# Controller.net
KiCad netlist of a schematic drawn in EAGLE
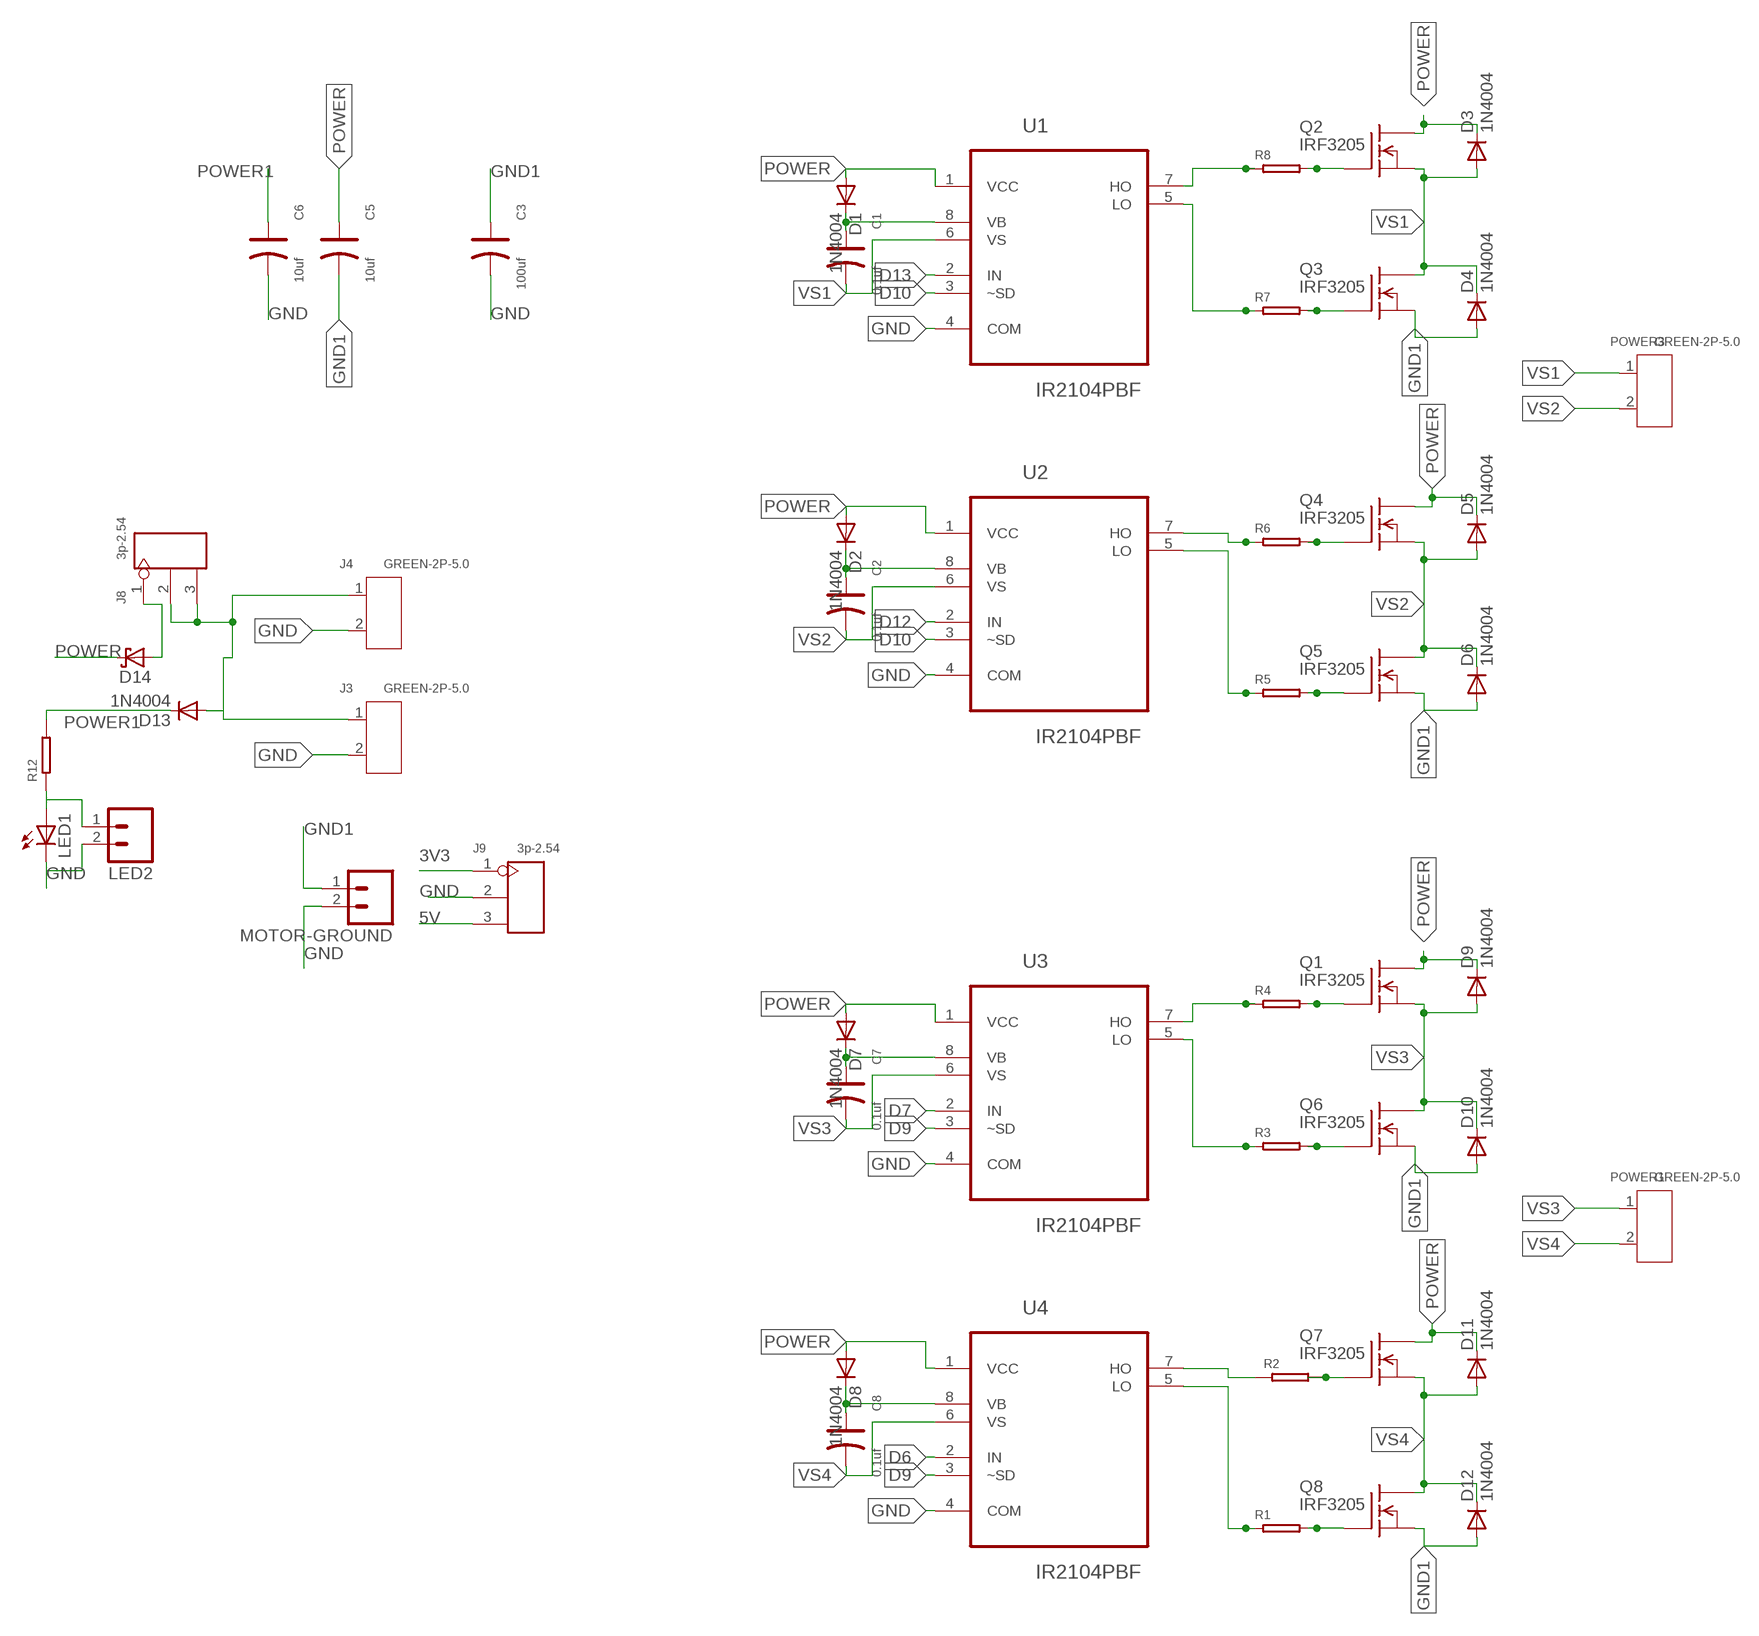
[diagram p0: schematic, sheet 1, part 1 of 2]
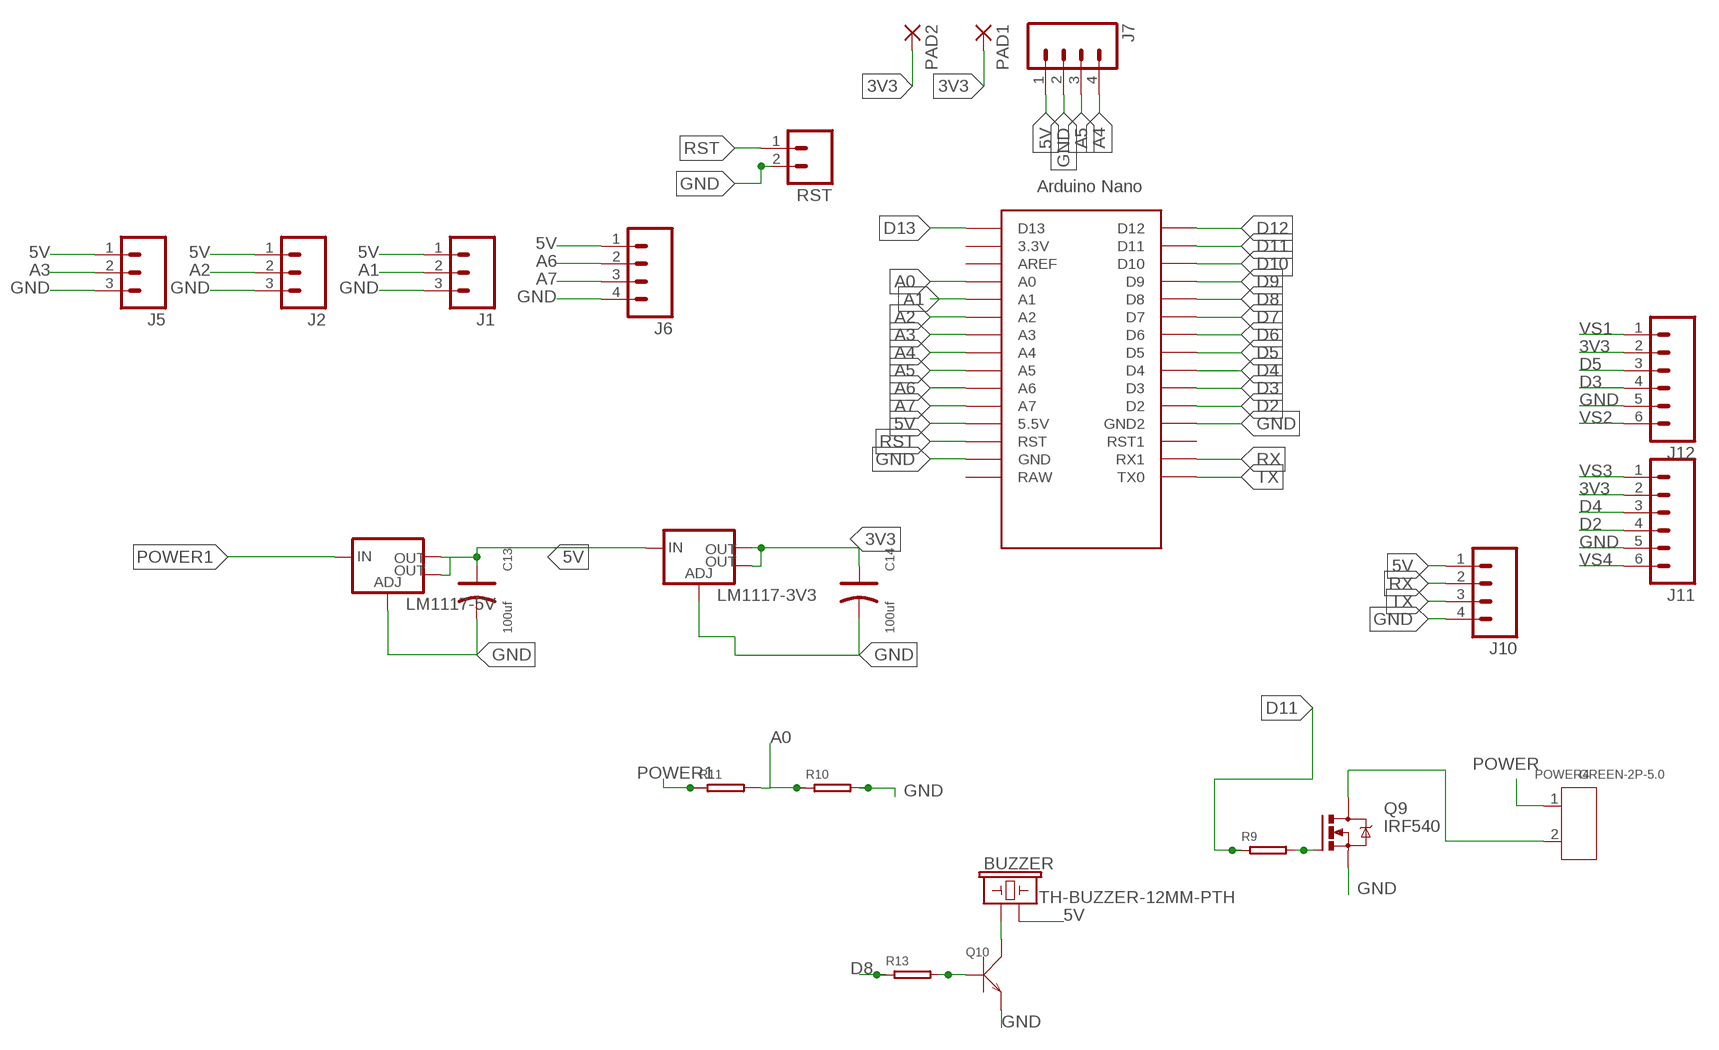
[diagram p1: schematic, sheet 1, part 2 of 2]

(export (version "E")
  (design (tool "Eeschema 10.0.6"))
  (components
    (comp (ref "BUZZER")
      (value "TH-BUZZER-12MM-PTH")
      (footprint "eagle-import:BUZZER-12MM")
      (libsource (lib "eagle-import") (part "TH-BUZZER-12MM-PTH"))
    )
    (comp (ref "C1")
      (value "0.1uf")
      (footprint "eagle-import:PC-D5.3MM")
      (fields (field (name "MPN") "KS 100uF/16V"))
      (libsource (lib "eagle-import") (part "DIP-ALUMINUM-100UF-16V(D5-H7MM)"))
    )
    (comp (ref "C2")
      (value "0.1uf")
      (footprint "eagle-import:PC-D5.3MM")
      (fields (field (name "MPN") "KS 100uF/16V"))
      (libsource (lib "eagle-import") (part "DIP-ALUMINUM-100UF-16V(D5-H7MM)"))
    )
    (comp (ref "C3")
      (value "100uf")
      (footprint "eagle-import:PC-D5.3MM")
      (fields (field (name "MPN") "KS 100uF/16V"))
      (libsource (lib "eagle-import") (part "DIP-ALUMINUM-100UF-16V(D5-H7MM)"))
    )
    (comp (ref "C5")
      (value "10uf")
      (footprint "eagle-import:PC-D5.3MM")
      (fields (field (name "MPN") "KS 100uF/16V"))
      (libsource (lib "eagle-import") (part "DIP-ALUMINUM-100UF-16V(D5-H7MM)"))
    )
    (comp (ref "C6")
      (value "10uf")
      (footprint "eagle-import:PC-D5.3MM")
      (fields (field (name "MPN") "KS 100uF/16V"))
      (libsource (lib "eagle-import") (part "DIP-ALUMINUM-100UF-16V(D5-H7MM)"))
    )
    (comp (ref "C7")
      (value "0.1uf")
      (footprint "eagle-import:PC-D5.3MM")
      (fields (field (name "MPN") "KS 100uF/16V"))
      (libsource (lib "eagle-import") (part "DIP-ALUMINUM-100UF-16V(D5-H7MM)"))
    )
    (comp (ref "C8")
      (value "0.1uf")
      (footprint "eagle-import:PC-D5.3MM")
      (fields (field (name "MPN") "KS 100uF/16V"))
      (libsource (lib "eagle-import") (part "DIP-ALUMINUM-100UF-16V(D5-H7MM)"))
    )
    (comp (ref "C13")
      (value "100uf")
      (footprint "eagle-import:PC-D5.3MM")
      (fields (field (name "MPN") "KS 100uF/16V"))
      (libsource (lib "eagle-import") (part "DIP-ALUMINUM-100UF-16V(D5-H7MM)"))
    )
    (comp (ref "C14")
      (value "100uf")
      (footprint "eagle-import:PC-D5.3MM")
      (fields (field (name "MPN") "KS 100uF/16V"))
      (libsource (lib "eagle-import") (part "DIP-ALUMINUM-100UF-16V(D5-H7MM)"))
    )
    (comp (ref "D1")
      (value "1N4004")
      (footprint "eagle-import:DO41-10")
      (libsource (lib "eagle-import") (part "1N4004"))
    )
    (comp (ref "D2")
      (value "1N4004")
      (footprint "eagle-import:DO41-10")
      (libsource (lib "eagle-import") (part "1N4004"))
    )
    (comp (ref "D3")
      (value "1N4004")
      (footprint "eagle-import:DO41-10")
      (libsource (lib "eagle-import") (part "1N4004"))
    )
    (comp (ref "D4")
      (value "1N4004")
      (footprint "eagle-import:DO41-10")
      (libsource (lib "eagle-import") (part "1N4004"))
    )
    (comp (ref "D5")
      (value "1N4004")
      (footprint "eagle-import:DO41-10")
      (libsource (lib "eagle-import") (part "1N4004"))
    )
    (comp (ref "D6")
      (value "1N4004")
      (footprint "eagle-import:DO41-10")
      (libsource (lib "eagle-import") (part "1N4004"))
    )
    (comp (ref "D7")
      (value "1N4004")
      (footprint "eagle-import:DO41-10")
      (libsource (lib "eagle-import") (part "1N4004"))
    )
    (comp (ref "D8")
      (value "1N4004")
      (footprint "eagle-import:DO41-10")
      (libsource (lib "eagle-import") (part "1N4004"))
    )
    (comp (ref "D9")
      (value "1N4004")
      (footprint "eagle-import:DO41-10")
      (libsource (lib "eagle-import") (part "1N4004"))
    )
    (comp (ref "D10")
      (value "1N4004")
      (footprint "eagle-import:DO41-10")
      (libsource (lib "eagle-import") (part "1N4004"))
    )
    (comp (ref "D11")
      (value "1N4004")
      (footprint "eagle-import:DO41-10")
      (libsource (lib "eagle-import") (part "1N4004"))
    )
    (comp (ref "D12")
      (value "1N4004")
      (footprint "eagle-import:DO41-10")
      (libsource (lib "eagle-import") (part "1N4004"))
    )
    (comp (ref "D13")
      (value "1N4004")
      (footprint "eagle-import:DO41-10")
      (libsource (lib "eagle-import") (part "1N4004"))
    )
    (comp (ref "D14")
      (value "SCHOTTKY-DIODEDO201T15")
      (footprint "eagle-import:DO201T15")
      (libsource (lib "eagle-import") (part "SCHOTTKY-DIODEDO201T15"))
    )
    (comp (ref "J1")
      (value "M03POLAR")
      (footprint "eagle-import:MOLEX-1X3")
      (libsource (lib "eagle-import") (part "M03POLAR"))
    )
    (comp (ref "J2")
      (value "M03POLAR")
      (footprint "eagle-import:MOLEX-1X3")
      (libsource (lib "eagle-import") (part "M03POLAR"))
    )
    (comp (ref "J3")
      (value "GREEN-2P-5.0")
      (footprint "eagle-import:H2-5.0-10.5X8.0MM")
      (libsource (lib "eagle-import") (part "Seeed-OPL-Connector_SCREW-TERMINAL-GREEN(2P-5.0)"))
    )
    (comp (ref "J4")
      (value "GREEN-2P-5.0")
      (footprint "eagle-import:H2-5.0-10.5X8.0MM")
      (libsource (lib "eagle-import") (part "Seeed-OPL-Connector_SCREW-TERMINAL-GREEN(2P-5.0)"))
    )
    (comp (ref "J5")
      (value "M03POLAR")
      (footprint "eagle-import:MOLEX-1X3")
      (libsource (lib "eagle-import") (part "M03POLAR"))
    )
    (comp (ref "J6")
      (value "M04POLAR")
      (footprint "eagle-import:MOLEX-1X4")
      (libsource (lib "eagle-import") (part "M04POLAR"))
    )
    (comp (ref "J7")
      (value "M04POLAR")
      (footprint "eagle-import:MOLEX-1X4")
      (libsource (lib "eagle-import") (part "M04POLAR"))
    )
    (comp (ref "J8")
      (value "3p-2.54")
      (footprint "eagle-import:H3-2.54")
      (fields (field (name "MPN") "F185-1103A0BSYA1"))
      (libsource (lib "eagle-import") (part "DIP-BLACK-FEMALE-HEADER-VERT(3P-2.54)"))
    )
    (comp (ref "J9")
      (value "3p-2.54")
      (footprint "eagle-import:H3-2.54")
      (fields (field (name "MPN") "F185-1103A0BSYA1"))
      (libsource (lib "eagle-import") (part "DIP-BLACK-FEMALE-HEADER-VERT(3P-2.54)"))
    )
    (comp (ref "J10")
      (value "M04POLAR")
      (footprint "eagle-import:MOLEX-1X4")
      (libsource (lib "eagle-import") (part "M04POLAR"))
    )
    (comp (ref "J11")
      (value "M06POLAR")
      (footprint "eagle-import:MOLEX-1X6")
      (libsource (lib "eagle-import") (part "M06POLAR"))
    )
    (comp (ref "J12")
      (value "M06POLAR")
      (footprint "eagle-import:MOLEX-1X6")
      (libsource (lib "eagle-import") (part "M06POLAR"))
    )
    (comp (ref "LED1")
      (value "LEDCHIPLED_0603")
      (footprint "eagle-import:CHIPLED_0603")
      (libsource (lib "eagle-import") (part "LEDCHIPLED_0603"))
    )
    (comp (ref "LED2")
      (value "M02PTH")
      (footprint "eagle-import:1X02")
      (libsource (lib "eagle-import") (part "M02PTH"))
    )
    (comp (ref "LM1117-3V3")
      (value "V_REG_LM1117SOT223")
      (footprint "eagle-import:SOT223")
      (libsource (lib "eagle-import") (part "V_REG_LM1117SOT223"))
    )
    (comp (ref "LM1117-5V")
      (value "V_REG_LM1117SOT223")
      (footprint "eagle-import:SOT223")
      (libsource (lib "eagle-import") (part "V_REG_LM1117SOT223"))
    )
    (comp (ref "MOTOR-GROUND")
      (value "M02PTH")
      (footprint "eagle-import:1X02")
      (libsource (lib "eagle-import") (part "M02PTH"))
    )
    (comp (ref "PAD1")
      (value "2,15/1,0")
      (footprint "eagle-import:2,15_1,0")
      (libsource (lib "eagle-import") (part "2,15/1,0"))
    )
    (comp (ref "PAD2")
      (value "2,15/1,0")
      (footprint "eagle-import:2,15_1,0")
      (libsource (lib "eagle-import") (part "2,15/1,0"))
    )
    (comp (ref "POWER1")
      (value "GREEN-2P-5.0")
      (footprint "eagle-import:H2-5.0-10.5X8.0MM")
      (libsource (lib "eagle-import") (part "SCREW-TERMINAL-GREEN(2P-5.0)"))
    )
    (comp (ref "POWER3")
      (value "GREEN-2P-5.0")
      (footprint "eagle-import:H2-5.0-10.5X8.0MM")
      (libsource (lib "eagle-import") (part "SCREW-TERMINAL-GREEN(2P-5.0)"))
    )
    (comp (ref "POWER4")
      (value "GREEN-2P-5.0")
      (footprint "eagle-import:H2-5.0-10.5X8.0MM")
      (libsource (lib "eagle-import") (part "SCREW-TERMINAL-GREEN(2P-5.0)"))
    )
    (comp (ref "Q1")
      (value "IRF3205")
      (footprint "eagle-import:TO220")
      (libsource (lib "eagle-import") (part "IRF540"))
    )
    (comp (ref "Q2")
      (value "IRF3205")
      (footprint "eagle-import:TO220")
      (libsource (lib "eagle-import") (part "IRF540"))
    )
    (comp (ref "Q3")
      (value "IRF3205")
      (footprint "eagle-import:TO220")
      (libsource (lib "eagle-import") (part "IRF540"))
    )
    (comp (ref "Q4")
      (value "IRF3205")
      (footprint "eagle-import:TO220")
      (libsource (lib "eagle-import") (part "IRF540"))
    )
    (comp (ref "Q5")
      (value "IRF3205")
      (footprint "eagle-import:TO220")
      (libsource (lib "eagle-import") (part "IRF540"))
    )
    (comp (ref "Q6")
      (value "IRF3205")
      (footprint "eagle-import:TO220")
      (libsource (lib "eagle-import") (part "IRF540"))
    )
    (comp (ref "Q7")
      (value "IRF3205")
      (footprint "eagle-import:TO220")
      (libsource (lib "eagle-import") (part "IRF540"))
    )
    (comp (ref "Q8")
      (value "IRF3205")
      (footprint "eagle-import:TO220")
      (libsource (lib "eagle-import") (part "IRF540"))
    )
    (comp (ref "Q9")
      (value "IRF540")
      (footprint "eagle-import:TO220BV")
      (libsource (lib "eagle-import") (part "transistor-power_IRF540"))
    )
    (comp (ref "Q10")
      (value "SMD-TRANSISTOR-NPN-SOT-23")
      (footprint "eagle-import:SOT-23")
      (libsource (lib "eagle-import") (part "SMD-TRANSISTOR-NPN-SOT-23"))
    )
    (comp (ref "R1")
      (value "SMD-RESISTOR-0603")
      (footprint "eagle-import:R0603")
      (libsource (lib "eagle-import") (part "SMD-RESISTOR-0603"))
    )
    (comp (ref "R2")
      (value "SMD-RESISTOR-0603")
      (footprint "eagle-import:R0603")
      (libsource (lib "eagle-import") (part "SMD-RESISTOR-0603"))
    )
    (comp (ref "R3")
      (value "SMD-RESISTOR-0603")
      (footprint "eagle-import:R0603")
      (libsource (lib "eagle-import") (part "SMD-RESISTOR-0603"))
    )
    (comp (ref "R4")
      (value "SMD-RESISTOR-0603")
      (footprint "eagle-import:R0603")
      (libsource (lib "eagle-import") (part "SMD-RESISTOR-0603"))
    )
    (comp (ref "R5")
      (value "SMD-RESISTOR-0603")
      (footprint "eagle-import:R0603")
      (libsource (lib "eagle-import") (part "SMD-RESISTOR-0603"))
    )
    (comp (ref "R6")
      (value "SMD-RESISTOR-0603")
      (footprint "eagle-import:R0603")
      (libsource (lib "eagle-import") (part "SMD-RESISTOR-0603"))
    )
    (comp (ref "R7")
      (value "SMD-RESISTOR-0603")
      (footprint "eagle-import:R0603")
      (libsource (lib "eagle-import") (part "SMD-RESISTOR-0603"))
    )
    (comp (ref "R8")
      (value "SMD-RESISTOR-0603")
      (footprint "eagle-import:R0603")
      (libsource (lib "eagle-import") (part "SMD-RESISTOR-0603"))
    )
    (comp (ref "R9")
      (value "SMD-RESISTOR-0603")
      (footprint "eagle-import:R0603")
      (libsource (lib "eagle-import") (part "SMD-RESISTOR-0603"))
    )
    (comp (ref "R10")
      (value "SMD-RESISTOR-0603")
      (footprint "eagle-import:R0603")
      (libsource (lib "eagle-import") (part "SMD-RESISTOR-0603"))
    )
    (comp (ref "R11")
      (value "SMD-RESISTOR-0603")
      (footprint "eagle-import:R0603")
      (libsource (lib "eagle-import") (part "SMD-RESISTOR-0603"))
    )
    (comp (ref "R12")
      (value "SMD-RESISTOR-0603")
      (footprint "eagle-import:R0603")
      (libsource (lib "eagle-import") (part "SMD-RESISTOR-0603"))
    )
    (comp (ref "R13")
      (value "SMD-RESISTOR-0603")
      (footprint "eagle-import:R0603")
      (libsource (lib "eagle-import") (part "SMD-RESISTOR-0603"))
    )
    (comp (ref "RST")
      (value "M02PTH")
      (footprint "eagle-import:1X02")
      (libsource (lib "eagle-import") (part "M02PTH"))
    )
    (comp (ref "U$1")
      (value "NANO")
      (footprint "eagle-import:NANO")
      (libsource (lib "eagle-import") (part "NANO"))
    )
    (comp (ref "U1")
      (value "IR2104PBF")
      (footprint "eagle-import:DIP254P762X533-8")
      (libsource (lib "eagle-import") (part "IR2104PBF"))
    )
    (comp (ref "U2")
      (value "IR2104PBF")
      (footprint "eagle-import:DIP254P762X533-8")
      (libsource (lib "eagle-import") (part "IR2104PBF"))
    )
    (comp (ref "U3")
      (value "IR2104PBF")
      (footprint "eagle-import:DIP254P762X533-8")
      (libsource (lib "eagle-import") (part "IR2104PBF"))
    )
    (comp (ref "U4")
      (value "IR2104PBF")
      (footprint "eagle-import:DIP254P762X533-8")
      (libsource (lib "eagle-import") (part "IR2104PBF"))
    )
  )
  (nets
    (net (code "1") (name "3V3") (class "Default")
      (node (ref "C14") (pin "+") (pinfunction "+_+") (pintype "passive"))
      (node (ref "J11") (pin "2") (pinfunction "2_2") (pintype "passive"))
      (node (ref "J12") (pin "2") (pinfunction "2_2") (pintype "passive"))
      (node (ref "J9") (pin "1") (pinfunction "P$1_1") (pintype "bidirectional"))
      (node (ref "LM1117-3V3") (pin "2") (pinfunction "OUT_2") (pintype "output"))
      (node (ref "LM1117-3V3") (pin "4") (pinfunction "OUT_4") (pintype "output"))
      (node (ref "PAD1") (pin "1") (pinfunction "P_1") (pintype "passive"))
      (node (ref "PAD2") (pin "1") (pinfunction "P_1") (pintype "passive"))
    )
    (net (code "2") (name "5V") (class "Default")
      (node (ref "BUZZER") (pin "-") (pinfunction "2_-") (pintype "passive"))
      (node (ref "C13") (pin "+") (pinfunction "+_+") (pintype "passive"))
      (node (ref "J1") (pin "1") (pinfunction "1_1") (pintype "passive"))
      (node (ref "J10") (pin "1") (pinfunction "1_1") (pintype "passive"))
      (node (ref "J2") (pin "1") (pinfunction "1_1") (pintype "passive"))
      (node (ref "J5") (pin "1") (pinfunction "1_1") (pintype "passive"))
      (node (ref "J6") (pin "1") (pinfunction "1_1") (pintype "passive"))
      (node (ref "J7") (pin "1") (pinfunction "1_1") (pintype "passive"))
      (node (ref "J9") (pin "3") (pinfunction "P$3_3") (pintype "bidirectional"))
      (node (ref "LM1117-3V3") (pin "3") (pinfunction "IN_3") (pintype "input"))
      (node (ref "LM1117-5V") (pin "2") (pinfunction "OUT_2") (pintype "output"))
      (node (ref "LM1117-5V") (pin "4") (pinfunction "OUT_4") (pintype "output"))
      (node (ref "U$1") (pin "5V") (pinfunction "5.5V_5V") (pintype "bidirectional"))
    )
    (net (code "3") (name "A0") (class "Default")
      (node (ref "R10") (pin "1") (pinfunction "1_1") (pintype "passive"))
      (node (ref "R11") (pin "2") (pinfunction "2_2") (pintype "passive"))
      (node (ref "U$1") (pin "A0") (pinfunction "A0_A0") (pintype "bidirectional"))
    )
    (net (code "4") (name "A1") (class "Default")
      (node (ref "J1") (pin "2") (pinfunction "2_2") (pintype "passive"))
      (node (ref "U$1") (pin "A1") (pinfunction "A1_A1") (pintype "bidirectional"))
    )
    (net (code "5") (name "A2") (class "Default")
      (node (ref "J2") (pin "2") (pinfunction "2_2") (pintype "passive"))
      (node (ref "U$1") (pin "A2") (pinfunction "A2_A2") (pintype "bidirectional"))
    )
    (net (code "6") (name "A3") (class "Default")
      (node (ref "J5") (pin "2") (pinfunction "2_2") (pintype "passive"))
      (node (ref "U$1") (pin "A3") (pinfunction "A3_A3") (pintype "bidirectional"))
    )
    (net (code "7") (name "A4") (class "Default")
      (node (ref "J7") (pin "4") (pinfunction "4_4") (pintype "passive"))
      (node (ref "U$1") (pin "A4") (pinfunction "A4_A4") (pintype "bidirectional"))
    )
    (net (code "8") (name "A5") (class "Default")
      (node (ref "J7") (pin "3") (pinfunction "3_3") (pintype "passive"))
      (node (ref "U$1") (pin "A5") (pinfunction "A5_A5") (pintype "bidirectional"))
    )
    (net (code "9") (name "A6") (class "Default")
      (node (ref "J6") (pin "2") (pinfunction "2_2") (pintype "passive"))
      (node (ref "U$1") (pin "A6") (pinfunction "A6_A6") (pintype "bidirectional"))
    )
    (net (code "10") (name "A7") (class "Default")
      (node (ref "J6") (pin "3") (pinfunction "3_3") (pintype "passive"))
      (node (ref "U$1") (pin "A7") (pinfunction "A7_A7") (pintype "bidirectional"))
    )
    (net (code "11") (name "D2") (class "Default")
      (node (ref "J11") (pin "4") (pinfunction "4_4") (pintype "passive"))
      (node (ref "U$1") (pin "D2") (pinfunction "D2_D2") (pintype "bidirectional"))
    )
    (net (code "12") (name "D3") (class "Default")
      (node (ref "J12") (pin "4") (pinfunction "4_4") (pintype "passive"))
      (node (ref "U$1") (pin "D3") (pinfunction "D3_D3") (pintype "bidirectional"))
    )
    (net (code "13") (name "D4") (class "Default")
      (node (ref "J11") (pin "3") (pinfunction "3_3") (pintype "passive"))
      (node (ref "U$1") (pin "D4") (pinfunction "D4_D4") (pintype "bidirectional"))
    )
    (net (code "14") (name "D5") (class "Default")
      (node (ref "J12") (pin "3") (pinfunction "3_3") (pintype "passive"))
      (node (ref "U$1") (pin "D5") (pinfunction "D5_D5") (pintype "bidirectional"))
    )
    (net (code "15") (name "D6") (class "Default")
      (node (ref "U$1") (pin "D6") (pinfunction "D6_D6") (pintype "bidirectional"))
      (node (ref "U4") (pin "2") (pinfunction "IN_2") (pintype "input"))
    )
    (net (code "16") (name "D7") (class "Default")
      (node (ref "U$1") (pin "D7") (pinfunction "D7_D7") (pintype "bidirectional"))
      (node (ref "U3") (pin "2") (pinfunction "IN_2") (pintype "input"))
    )
    (net (code "17") (name "D8") (class "Default")
      (node (ref "R13") (pin "1") (pinfunction "1_1") (pintype "passive"))
      (node (ref "U$1") (pin "D8") (pinfunction "D8_D8") (pintype "bidirectional"))
    )
    (net (code "18") (name "D9") (class "Default")
      (node (ref "U$1") (pin "D9") (pinfunction "D9_D9") (pintype "bidirectional"))
      (node (ref "U3") (pin "3") (pinfunction "~{SD}_3") (pintype "input"))
      (node (ref "U4") (pin "3") (pinfunction "~{SD}_3") (pintype "input"))
    )
    (net (code "19") (name "D10") (class "Default")
      (node (ref "U$1") (pin "D10") (pinfunction "D10_D10") (pintype "bidirectional"))
      (node (ref "U1") (pin "3") (pinfunction "~{SD}_3") (pintype "input"))
      (node (ref "U2") (pin "3") (pinfunction "~{SD}_3") (pintype "input"))
    )
    (net (code "20") (name "D11") (class "Default")
      (node (ref "R9") (pin "1") (pinfunction "1_1") (pintype "passive"))
      (node (ref "U$1") (pin "D11") (pinfunction "D11_D11") (pintype "bidirectional"))
    )
    (net (code "21") (name "D12") (class "Default")
      (node (ref "U$1") (pin "D12") (pinfunction "D12_D12") (pintype "bidirectional"))
      (node (ref "U2") (pin "2") (pinfunction "IN_2") (pintype "input"))
    )
    (net (code "22") (name "D13") (class "Default")
      (node (ref "U$1") (pin "D13") (pinfunction "D13_D13") (pintype "bidirectional"))
      (node (ref "U1") (pin "2") (pinfunction "IN_2") (pintype "input"))
    )
    (net (code "23") (name "GND") (class "Default")
      (node (ref "C13") (pin "-") (pinfunction "-_-") (pintype "passive"))
      (node (ref "C14") (pin "-") (pinfunction "-_-") (pintype "passive"))
      (node (ref "C3") (pin "-") (pinfunction "-_-") (pintype "passive"))
      (node (ref "C6") (pin "-") (pinfunction "-_-") (pintype "passive"))
      (node (ref "J1") (pin "3") (pinfunction "3_3") (pintype "passive"))
      (node (ref "J10") (pin "4") (pinfunction "4_4") (pintype "passive"))
      (node (ref "J11") (pin "5") (pinfunction "5_5") (pintype "passive"))
      (node (ref "J12") (pin "5") (pinfunction "5_5") (pintype "passive"))
      (node (ref "J2") (pin "3") (pinfunction "3_3") (pintype "passive"))
      (node (ref "J3") (pin "2") (pinfunction "2_2") (pintype "bidirectional"))
      (node (ref "J4") (pin "2") (pinfunction "2_2") (pintype "bidirectional"))
      (node (ref "J5") (pin "3") (pinfunction "3_3") (pintype "passive"))
      (node (ref "J6") (pin "4") (pinfunction "4_4") (pintype "passive"))
      (node (ref "J7") (pin "2") (pinfunction "2_2") (pintype "passive"))
      (node (ref "J9") (pin "2") (pinfunction "P$2_2") (pintype "bidirectional"))
      (node (ref "LED1") (pin "C") (pinfunction "C_C") (pintype "passive"))
      (node (ref "LED2") (pin "2") (pinfunction "2_2") (pintype "passive"))
      (node (ref "LM1117-3V3") (pin "1") (pinfunction "ADJ_1") (pintype "input"))
      (node (ref "LM1117-5V") (pin "1") (pinfunction "ADJ_1") (pintype "input"))
      (node (ref "MOTOR-GROUND") (pin "2") (pinfunction "2_2") (pintype "passive"))
      (node (ref "Q10") (pin "2") (pinfunction "E_2") (pintype "passive"))
      (node (ref "Q9") (pin "S") (pinfunction "S_S") (pintype "passive"))
      (node (ref "R10") (pin "2") (pinfunction "2_2") (pintype "passive"))
      (node (ref "RST") (pin "2") (pinfunction "2_2") (pintype "passive"))
      (node (ref "U$1") (pin "GND") (pinfunction "GND_GND") (pintype "bidirectional"))
      (node (ref "U$1") (pin "GND1") (pinfunction "GND2_GND1") (pintype "bidirectional"))
      (node (ref "U1") (pin "4") (pinfunction "COM_4") (pintype "input"))
      (node (ref "U2") (pin "4") (pinfunction "COM_4") (pintype "input"))
      (node (ref "U3") (pin "4") (pinfunction "COM_4") (pintype "input"))
      (node (ref "U4") (pin "4") (pinfunction "COM_4") (pintype "input"))
    )
    (net (code "24") (name "GND1") (class "Default")
      (node (ref "C3") (pin "+") (pinfunction "+_+") (pintype "passive"))
      (node (ref "C5") (pin "-") (pinfunction "-_-") (pintype "passive"))
      (node (ref "D10") (pin "A") (pinfunction "A_A") (pintype "passive"))
      (node (ref "D12") (pin "A") (pinfunction "A_A") (pintype "passive"))
      (node (ref "D4") (pin "A") (pinfunction "A_A") (pintype "passive"))
      (node (ref "D6") (pin "A") (pinfunction "A_A") (pintype "passive"))
      (node (ref "MOTOR-GROUND") (pin "1") (pinfunction "1_1") (pintype "passive"))
      (node (ref "Q3") (pin "3") (pinfunction "S_3") (pintype "passive"))
      (node (ref "Q5") (pin "3") (pinfunction "S_3") (pintype "passive"))
      (node (ref "Q6") (pin "3") (pinfunction "S_3") (pintype "passive"))
      (node (ref "Q8") (pin "3") (pinfunction "S_3") (pintype "passive"))
    )
    (net (code "25") (name "Net-(BUZZER-1)") (class "Default")
      (node (ref "BUZZER") (pin "+") (pinfunction "1_+") (pintype "passive"))
      (node (ref "Q10") (pin "3") (pinfunction "C_3") (pintype "passive"))
    )
    (net (code "26") (name "Net-(J8-P$1)") (class "Default")
      (node (ref "D14") (pin "A") (pinfunction "A_A") (pintype "passive"))
      (node (ref "J8") (pin "1") (pinfunction "P$1_1") (pintype "bidirectional"))
    )
    (net (code "27") (name "Net-(J8-P$2)") (class "Default")
      (node (ref "D13") (pin "A") (pinfunction "A_A") (pintype "passive"))
      (node (ref "J3") (pin "1") (pinfunction "1_1") (pintype "bidirectional"))
      (node (ref "J4") (pin "1") (pinfunction "1_1") (pintype "bidirectional"))
      (node (ref "J8") (pin "2") (pinfunction "P$2_2") (pintype "bidirectional"))
      (node (ref "J8") (pin "3") (pinfunction "P$3_3") (pintype "bidirectional"))
    )
    (net (code "28") (name "Net-(LED1-PadA)") (class "Default")
      (node (ref "LED1") (pin "A") (pinfunction "A_A") (pintype "passive"))
      (node (ref "LED2") (pin "1") (pinfunction "1_1") (pintype "passive"))
      (node (ref "R12") (pin "1") (pinfunction "1_1") (pintype "passive"))
    )
    (net (code "29") (name "Net-(POWER4-Pad2)") (class "Default")
      (node (ref "POWER4") (pin "2") (pinfunction "2_2") (pintype "bidirectional"))
      (node (ref "Q9") (pin "D") (pinfunction "D_D") (pintype "passive"))
    )
    (net (code "30") (name "Net-(Q1-G)") (class "Default")
      (node (ref "Q1") (pin "1") (pinfunction "G_1") (pintype "passive"))
      (node (ref "R4") (pin "2") (pinfunction "2_2") (pintype "passive"))
    )
    (net (code "31") (name "Net-(Q2-G)") (class "Default")
      (node (ref "Q2") (pin "1") (pinfunction "G_1") (pintype "passive"))
      (node (ref "R8") (pin "2") (pinfunction "2_2") (pintype "passive"))
    )
    (net (code "32") (name "Net-(Q3-G)") (class "Default")
      (node (ref "Q3") (pin "1") (pinfunction "G_1") (pintype "passive"))
      (node (ref "R7") (pin "2") (pinfunction "2_2") (pintype "passive"))
    )
    (net (code "33") (name "Net-(Q4-G)") (class "Default")
      (node (ref "Q4") (pin "1") (pinfunction "G_1") (pintype "passive"))
      (node (ref "R6") (pin "2") (pinfunction "2_2") (pintype "passive"))
    )
    (net (code "34") (name "Net-(Q5-G)") (class "Default")
      (node (ref "Q5") (pin "1") (pinfunction "G_1") (pintype "passive"))
      (node (ref "R5") (pin "2") (pinfunction "2_2") (pintype "passive"))
    )
    (net (code "35") (name "Net-(Q6-G)") (class "Default")
      (node (ref "Q6") (pin "1") (pinfunction "G_1") (pintype "passive"))
      (node (ref "R3") (pin "2") (pinfunction "2_2") (pintype "passive"))
    )
    (net (code "36") (name "Net-(Q7-G)") (class "Default")
      (node (ref "Q7") (pin "1") (pinfunction "G_1") (pintype "passive"))
      (node (ref "R2") (pin "2") (pinfunction "2_2") (pintype "passive"))
    )
    (net (code "37") (name "Net-(Q8-G)") (class "Default")
      (node (ref "Q8") (pin "1") (pinfunction "G_1") (pintype "passive"))
      (node (ref "R1") (pin "2") (pinfunction "2_2") (pintype "passive"))
    )
    (net (code "38") (name "Net-(Q9-PadG)") (class "Default")
      (node (ref "Q9") (pin "G") (pinfunction "G_G") (pintype "passive"))
      (node (ref "R9") (pin "2") (pinfunction "2_2") (pintype "passive"))
    )
    (net (code "39") (name "Net-(Q10-B)") (class "Default")
      (node (ref "Q10") (pin "1") (pinfunction "B_1") (pintype "passive"))
      (node (ref "R13") (pin "2") (pinfunction "2_2") (pintype "passive"))
    )
    (net (code "40") (name "Net-(U1-HO)") (class "Default")
      (node (ref "R8") (pin "1") (pinfunction "1_1") (pintype "passive"))
      (node (ref "U1") (pin "7") (pinfunction "HO_7") (pintype "output"))
    )
    (net (code "41") (name "Net-(U1-LO)") (class "Default")
      (node (ref "R7") (pin "1") (pinfunction "1_1") (pintype "passive"))
      (node (ref "U1") (pin "5") (pinfunction "LO_5") (pintype "output"))
    )
    (net (code "42") (name "Net-(U1-VB)") (class "Default")
      (node (ref "C1") (pin "+") (pinfunction "+_+") (pintype "passive"))
      (node (ref "D1") (pin "C") (pinfunction "C_C") (pintype "passive"))
      (node (ref "U1") (pin "8") (pinfunction "VB_8") (pintype "power_in"))
    )
    (net (code "43") (name "Net-(U2-HO)") (class "Default")
      (node (ref "R6") (pin "1") (pinfunction "1_1") (pintype "passive"))
      (node (ref "U2") (pin "7") (pinfunction "HO_7") (pintype "output"))
    )
    (net (code "44") (name "Net-(U2-LO)") (class "Default")
      (node (ref "R5") (pin "1") (pinfunction "1_1") (pintype "passive"))
      (node (ref "U2") (pin "5") (pinfunction "LO_5") (pintype "output"))
    )
    (net (code "45") (name "Net-(U2-VB)") (class "Default")
      (node (ref "C2") (pin "+") (pinfunction "+_+") (pintype "passive"))
      (node (ref "D2") (pin "C") (pinfunction "C_C") (pintype "passive"))
      (node (ref "U2") (pin "8") (pinfunction "VB_8") (pintype "power_in"))
    )
    (net (code "46") (name "Net-(U3-HO)") (class "Default")
      (node (ref "R4") (pin "1") (pinfunction "1_1") (pintype "passive"))
      (node (ref "U3") (pin "7") (pinfunction "HO_7") (pintype "output"))
    )
    (net (code "47") (name "Net-(U3-LO)") (class "Default")
      (node (ref "R3") (pin "1") (pinfunction "1_1") (pintype "passive"))
      (node (ref "U3") (pin "5") (pinfunction "LO_5") (pintype "output"))
    )
    (net (code "48") (name "Net-(U3-VB)") (class "Default")
      (node (ref "C7") (pin "+") (pinfunction "+_+") (pintype "passive"))
      (node (ref "D7") (pin "C") (pinfunction "C_C") (pintype "passive"))
      (node (ref "U3") (pin "8") (pinfunction "VB_8") (pintype "power_in"))
    )
    (net (code "49") (name "Net-(U4-HO)") (class "Default")
      (node (ref "R2") (pin "1") (pinfunction "1_1") (pintype "passive"))
      (node (ref "U4") (pin "7") (pinfunction "HO_7") (pintype "output"))
    )
    (net (code "50") (name "Net-(U4-LO)") (class "Default")
      (node (ref "R1") (pin "1") (pinfunction "1_1") (pintype "passive"))
      (node (ref "U4") (pin "5") (pinfunction "LO_5") (pintype "output"))
    )
    (net (code "51") (name "Net-(U4-VB)") (class "Default")
      (node (ref "C8") (pin "+") (pinfunction "+_+") (pintype "passive"))
      (node (ref "D8") (pin "C") (pinfunction "C_C") (pintype "passive"))
      (node (ref "U4") (pin "8") (pinfunction "VB_8") (pintype "power_in"))
    )
    (net (code "52") (name "POWER") (class "Default")
      (node (ref "C5") (pin "+") (pinfunction "+_+") (pintype "passive"))
      (node (ref "D1") (pin "A") (pinfunction "A_A") (pintype "passive"))
      (node (ref "D11") (pin "C") (pinfunction "C_C") (pintype "passive"))
      (node (ref "D14") (pin "C") (pinfunction "C_C") (pintype "passive"))
      (node (ref "D2") (pin "A") (pinfunction "A_A") (pintype "passive"))
      (node (ref "D3") (pin "C") (pinfunction "C_C") (pintype "passive"))
      (node (ref "D5") (pin "C") (pinfunction "C_C") (pintype "passive"))
      (node (ref "D7") (pin "A") (pinfunction "A_A") (pintype "passive"))
      (node (ref "D8") (pin "A") (pinfunction "A_A") (pintype "passive"))
      (node (ref "D9") (pin "C") (pinfunction "C_C") (pintype "passive"))
      (node (ref "POWER4") (pin "1") (pinfunction "1_1") (pintype "bidirectional"))
      (node (ref "Q1") (pin "2") (pinfunction "D_2") (pintype "passive"))
      (node (ref "Q2") (pin "2") (pinfunction "D_2") (pintype "passive"))
      (node (ref "Q4") (pin "2") (pinfunction "D_2") (pintype "passive"))
      (node (ref "Q7") (pin "2") (pinfunction "D_2") (pintype "passive"))
      (node (ref "U1") (pin "1") (pinfunction "VCC_1") (pintype "power_in"))
      (node (ref "U2") (pin "1") (pinfunction "VCC_1") (pintype "power_in"))
      (node (ref "U3") (pin "1") (pinfunction "VCC_1") (pintype "power_in"))
      (node (ref "U4") (pin "1") (pinfunction "VCC_1") (pintype "power_in"))
    )
    (net (code "53") (name "POWER1") (class "Default")
      (node (ref "C6") (pin "+") (pinfunction "+_+") (pintype "passive"))
      (node (ref "D13") (pin "C") (pinfunction "C_C") (pintype "passive"))
      (node (ref "LM1117-5V") (pin "3") (pinfunction "IN_3") (pintype "input"))
      (node (ref "R11") (pin "1") (pinfunction "1_1") (pintype "passive"))
      (node (ref "R12") (pin "2") (pinfunction "2_2") (pintype "passive"))
    )
    (net (code "54") (name "RST") (class "Default")
      (node (ref "RST") (pin "1") (pinfunction "1_1") (pintype "passive"))
      (node (ref "U$1") (pin "RST") (pinfunction "RST_RST") (pintype "bidirectional"))
    )
    (net (code "55") (name "RX") (class "Default")
      (node (ref "J10") (pin "2") (pinfunction "2_2") (pintype "passive"))
      (node (ref "U$1") (pin "RX1") (pinfunction "RX1_RX1") (pintype "bidirectional"))
    )
    (net (code "56") (name "TX") (class "Default")
      (node (ref "J10") (pin "3") (pinfunction "3_3") (pintype "passive"))
      (node (ref "U$1") (pin "TX0") (pinfunction "TX0_TX0") (pintype "bidirectional"))
    )
    (net (code "57") (name "VS1") (class "Default")
      (node (ref "C1") (pin "-") (pinfunction "-_-") (pintype "passive"))
      (node (ref "D3") (pin "A") (pinfunction "A_A") (pintype "passive"))
      (node (ref "D4") (pin "C") (pinfunction "C_C") (pintype "passive"))
      (node (ref "J12") (pin "1") (pinfunction "1_1") (pintype "passive"))
      (node (ref "POWER3") (pin "1") (pinfunction "1_1") (pintype "bidirectional"))
      (node (ref "Q2") (pin "3") (pinfunction "S_3") (pintype "passive"))
      (node (ref "Q3") (pin "2") (pinfunction "D_2") (pintype "passive"))
      (node (ref "U1") (pin "6") (pinfunction "VS_6") (pintype "power_in"))
    )
    (net (code "58") (name "VS2") (class "Default")
      (node (ref "C2") (pin "-") (pinfunction "-_-") (pintype "passive"))
      (node (ref "D5") (pin "A") (pinfunction "A_A") (pintype "passive"))
      (node (ref "D6") (pin "C") (pinfunction "C_C") (pintype "passive"))
      (node (ref "J12") (pin "6") (pinfunction "6_6") (pintype "passive"))
      (node (ref "POWER3") (pin "2") (pinfunction "2_2") (pintype "bidirectional"))
      (node (ref "Q4") (pin "3") (pinfunction "S_3") (pintype "passive"))
      (node (ref "Q5") (pin "2") (pinfunction "D_2") (pintype "passive"))
      (node (ref "U2") (pin "6") (pinfunction "VS_6") (pintype "power_in"))
    )
    (net (code "59") (name "VS3") (class "Default")
      (node (ref "C7") (pin "-") (pinfunction "-_-") (pintype "passive"))
      (node (ref "D10") (pin "C") (pinfunction "C_C") (pintype "passive"))
      (node (ref "D9") (pin "A") (pinfunction "A_A") (pintype "passive"))
      (node (ref "J11") (pin "1") (pinfunction "1_1") (pintype "passive"))
      (node (ref "POWER1") (pin "1") (pinfunction "1_1") (pintype "bidirectional"))
      (node (ref "Q1") (pin "3") (pinfunction "S_3") (pintype "passive"))
      (node (ref "Q6") (pin "2") (pinfunction "D_2") (pintype "passive"))
      (node (ref "U3") (pin "6") (pinfunction "VS_6") (pintype "power_in"))
    )
    (net (code "60") (name "VS4") (class "Default")
      (node (ref "C8") (pin "-") (pinfunction "-_-") (pintype "passive"))
      (node (ref "D11") (pin "A") (pinfunction "A_A") (pintype "passive"))
      (node (ref "D12") (pin "C") (pinfunction "C_C") (pintype "passive"))
      (node (ref "J11") (pin "6") (pinfunction "6_6") (pintype "passive"))
      (node (ref "POWER1") (pin "2") (pinfunction "2_2") (pintype "bidirectional"))
      (node (ref "Q7") (pin "3") (pinfunction "S_3") (pintype "passive"))
      (node (ref "Q8") (pin "2") (pinfunction "D_2") (pintype "passive"))
      (node (ref "U4") (pin "6") (pinfunction "VS_6") (pintype "power_in"))
    )
    (net (code "61") (name "unconnected-(U$1-Pad3.3V)") (class "Default")
      (node (ref "U$1") (pin "3.3V") (pinfunction "3.3V_3.3V") (pintype "bidirectional"))
    )
    (net (code "62") (name "unconnected-(U$1-PadAREF)") (class "Default")
      (node (ref "U$1") (pin "AREF") (pinfunction "AREF_AREF") (pintype "bidirectional"))
    )
    (net (code "63") (name "unconnected-(U$1-PadRAW)") (class "Default")
      (node (ref "U$1") (pin "RAW") (pinfunction "RAW_RAW") (pintype "bidirectional"))
    )
    (net (code "64") (name "unconnected-(U$1-PadRST1)") (class "Default")
      (node (ref "U$1") (pin "RST1") (pinfunction "RST1_RST1") (pintype "bidirectional"))
    )
  )
)
